# SCH-LM2596.net
KiCad netlist of a schematic drawn in Altium Designer
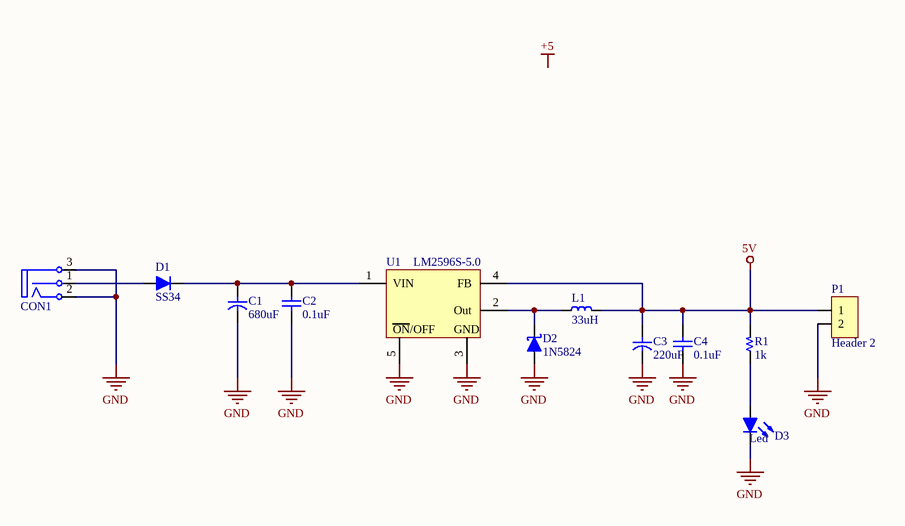
[diagram p0: SCH-LM2596.SchDoc]

(export (version "E")
  (design (tool "Eeschema 10.0.6"))
  (components
    (comp (ref "C1")
      (value "680uF")
      (footprint "CYL/D.500/LS.200")
      (description "Capacitor pol")
      (libsource (lib "chipfc_altium_libs") (part "Capacitor"))
    )
    (comp (ref "C2")
      (value "0.1uF")
      (footprint "C 0805")
      (description "Capacitor non-pol")
      (libsource (lib "chipfc_altium_libs") (part "Capacitor NP"))
    )
    (comp (ref "C3")
      (value "220uF")
      (footprint "CYL/D.500/LS.200")
      (description "Capacitor pol")
      (libsource (lib "chipfc_altium_libs") (part "Capacitor"))
    )
    (comp (ref "C4")
      (value "0.1uF")
      (footprint "C 0805")
      (description "Capacitor non-pol")
      (libsource (lib "chipfc_altium_libs") (part "Capacitor NP"))
    )
    (comp (ref "CON1")
      (value "CON DC PWR")
      (footprint "CONN/DC/PWR/5.0MM")
      (description "DC input connector")
      (libsource (lib "chipfc_altium_libs") (part "CON DC PWR"))
    )
    (comp (ref "D1")
      (value "SS34")
      (footprint "DO-214AC (SMA)")
      (description "Default Diode")
      (libsource (lib "chipfc_altium_libs") (part "Diode"))
    )
    (comp (ref "D2")
      (value "1N5824")
      (footprint "DO-214AC (SMA)")
      (description "Schottky Diode")
      (libsource (lib "chipfc_altium_libs") (part "Diode Schottky"))
    )
    (comp (ref "D3")
      (value "Led")
      (footprint "Led 0805 RED")
      (description "Typical LED")
      (libsource (lib "chipfc_altium_libs") (part "Led"))
    )
    (comp (ref "L1")
      (value "33uH")
      (footprint "Inductor SMD 12x12x8")
      (description "Inductor")
      (libsource (lib "chipfc_altium_libs") (part "Inductor"))
    )
    (comp (ref "P1")
      (value "Header 2")
      (footprint "HDR/Header/2/VH")
      (description "Header, 2-Pin")
      (libsource (lib "chipfc_altium_libs") (part "Header 2"))
    )
    (comp (ref "R1")
      (value "1k")
      (footprint "R 0805")
      (description "Resistor")
      (libsource (lib "chipfc_altium_libs") (part "Resistor"))
    )
    (comp (ref "U1")
      (value "LM2596S-5.0")
      (footprint "TO-263-5")
      (description "Simple Switcher 3A Step-Down Voltage Regulator")
      (libsource (lib "chipfc_altium_libs") (part "LM2596S-5.0"))
    )
  )
  (nets
    (net (code "2") (name "5V") (class "Default")
      (node (ref "C3") (pin "1") (pinfunction "1_1") (pintype "passive"))
      (node (ref "C4") (pin "1") (pinfunction "1_1") (pintype "passive"))
      (node (ref "L1") (pin "2") (pinfunction "2_2") (pintype "passive"))
      (node (ref "P1") (pin "1") (pinfunction "1_1") (pintype "passive"))
      (node (ref "R1") (pin "2") (pinfunction "2_2") (pintype "passive"))
      (node (ref "U1") (pin "4") (pinfunction "FB_4") (pintype "passive"))
    )
    (net (code "3") (name "GND") (class "Default")
      (node (ref "C1") (pin "2") (pinfunction "2_2") (pintype "passive"))
      (node (ref "C2") (pin "2") (pinfunction "2_2") (pintype "passive"))
      (node (ref "C3") (pin "2") (pinfunction "2_2") (pintype "passive"))
      (node (ref "C4") (pin "2") (pinfunction "2_2") (pintype "passive"))
      (node (ref "CON1") (pin "2") (pinfunction "T_2") (pintype "passive"))
      (node (ref "CON1") (pin "3") (pinfunction "TN_3") (pintype "passive"))
      (node (ref "D2") (pin "1") (pinfunction "A_1") (pintype "passive"))
      (node (ref "D3") (pin "2") (pinfunction "K_2") (pintype "passive"))
      (node (ref "P1") (pin "2") (pinfunction "2_2") (pintype "passive"))
      (node (ref "U1") (pin "3") (pinfunction "GND_3") (pintype "passive"))
      (node (ref "U1") (pin "5") (pinfunction "~{ON}/OFF_5") (pintype "passive"))
    )
    (net (code "4") (name "Net-(CON1-S)") (class "Default")
      (node (ref "CON1") (pin "1") (pinfunction "S_1") (pintype "power_in"))
      (node (ref "D1") (pin "1") (pinfunction "A_1") (pintype "passive"))
    )
    (net (code "5") (name "Net-(D1-K)") (class "Default")
      (node (ref "C1") (pin "1") (pinfunction "1_1") (pintype "passive"))
      (node (ref "C2") (pin "1") (pinfunction "1_1") (pintype "passive"))
      (node (ref "D1") (pin "2") (pinfunction "K_2") (pintype "passive"))
      (node (ref "U1") (pin "1") (pinfunction "VIN_1") (pintype "passive"))
    )
    (net (code "6") (name "Net-(D2-K)") (class "Default")
      (node (ref "D2") (pin "2") (pinfunction "K_2") (pintype "passive"))
      (node (ref "L1") (pin "1") (pinfunction "1_1") (pintype "passive"))
      (node (ref "U1") (pin "2") (pinfunction "Out_2") (pintype "passive"))
    )
    (net (code "7") (name "Net-(D3-A)") (class "Default")
      (node (ref "D3") (pin "1") (pinfunction "A_1") (pintype "passive"))
      (node (ref "R1") (pin "1") (pinfunction "1_1") (pintype "passive"))
    )
  )
)
